# attinier85-motherboard-smd-mk-2_2.net
KiCad netlist of a schematic drawn in EAGLE
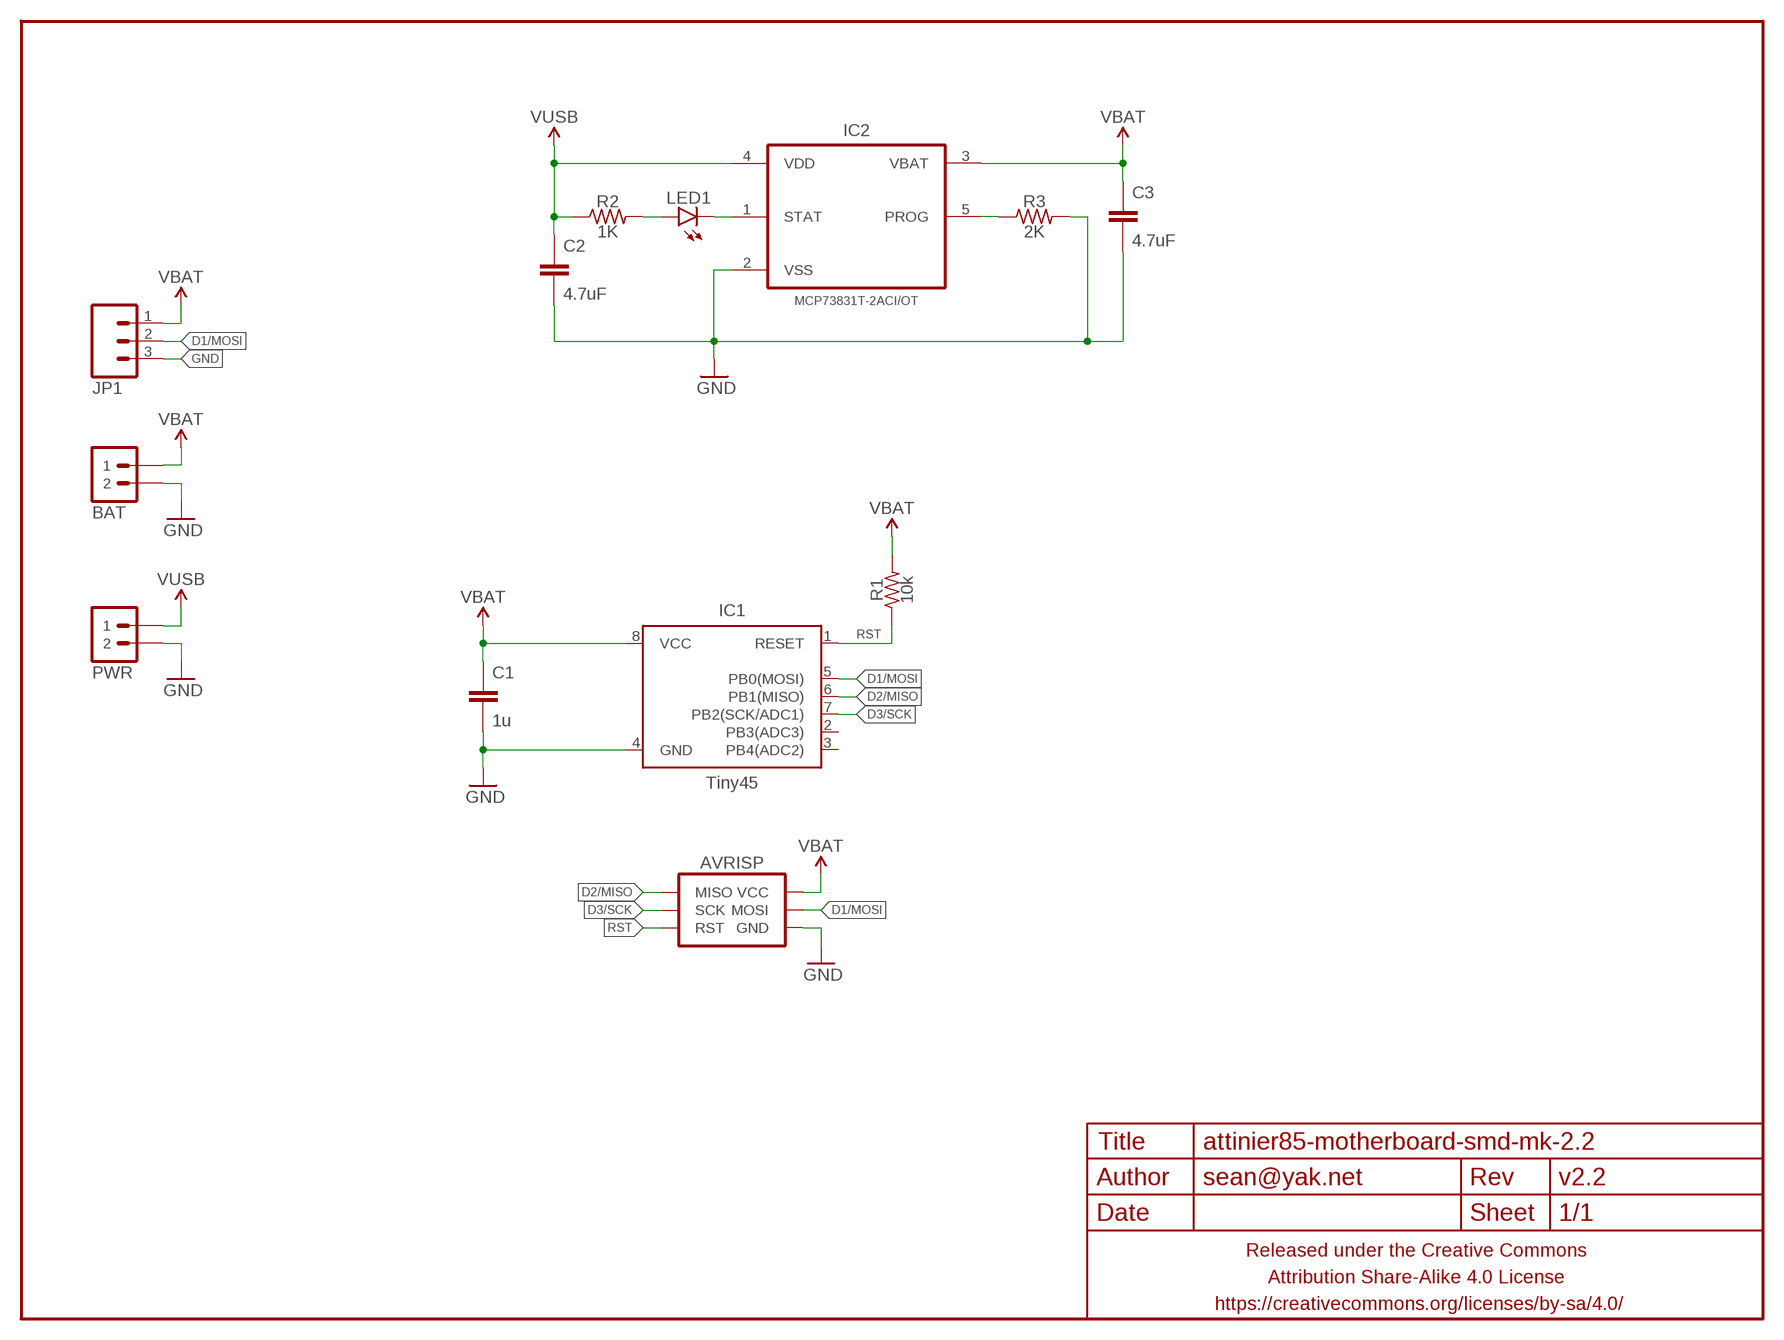
[diagram p0: schematic, sheet 1]

(export (version "E")
  (design (tool "Eeschema 10.0.6"))
  (components
    (comp (ref "AVRISP")
      (value "AVR_SPI_PRG_6SMD_TEST_POINTS")
      (footprint "eagle-import:2X3_SMD_TEST_POINTS")
      (libsource (lib "eagle-import") (part "AVR_SPI_PRG_6SMD_TEST_POINTS"))
    )
    (comp (ref "BAT")
      (value "M02PTH-CENTERED")
      (footprint "eagle-import:1X02-CENTER")
      (libsource (lib "eagle-import") (part "M02PTH-CENTERED"))
    )
    (comp (ref "C1")
      (value "1u")
      (footprint "eagle-import:C0603-TIGHTER")
      (libsource (lib "eagle-import") (part "CAPACITOR-CERAMICC0603-TIGHTER"))
    )
    (comp (ref "C2")
      (value "4.7uF")
      (footprint "eagle-import:C0603-TIGHTER")
      (libsource (lib "eagle-import") (part "CAPACITOR-CERAMICC0603-TIGHTER"))
    )
    (comp (ref "C3")
      (value "4.7uF")
      (footprint "eagle-import:C0603-TIGHTER")
      (libsource (lib "eagle-import") (part "CAPACITOR-CERAMICC0603-TIGHTER"))
    )
    (comp (ref "FRAME1")
      (value "FRAME-LETTERNO_PACKAGE")
      (footprint "eagle-import:DUMMY")
      (fields (field (name "DESIGNER") "sean@yak.net") (field (name "VERSION") "v2.2"))
      (libsource (lib "eagle-import") (part "FRAME-LETTERNO_PACKAGE"))
    )
    (comp (ref "IC1")
      (value "Tiny45")
      (footprint "eagle-import:SO08")
      (libsource (lib "eagle-import") (part "ATTINY45TINY25-20-SOICN"))
    )
    (comp (ref "IC2")
      (value "MCP73831T-2ACI/OT")
      (footprint "eagle-import:SOT95P280X145-5N")
      (libsource (lib "eagle-import") (part "MCP73831T-2ACI/OT"))
    )
    (comp (ref "JP1")
      (value "M03PTH-CENTERED")
      (footprint "eagle-import:1X03-CENTERED")
      (libsource (lib "eagle-import") (part "M03PTH-CENTERED"))
    )
    (comp (ref "LED1")
      (value "LED0603-TIGHT")
      (footprint "eagle-import:LED-0603-TIGHT")
      (libsource (lib "eagle-import") (part "LED0603-TIGHT"))
    )
    (comp (ref "PWR")
      (value "M02PTH-CENTERED")
      (footprint "eagle-import:1X02-CENTER")
      (libsource (lib "eagle-import") (part "M02PTH-CENTERED"))
    )
    (comp (ref "R1")
      (value "10k")
      (footprint "eagle-import:R0603-TIGHTER")
      (libsource (lib "eagle-import") (part "RESISTORR0603-TIGHTER"))
    )
    (comp (ref "R2")
      (value "1K")
      (footprint "eagle-import:R0603-TIGHTER")
      (libsource (lib "eagle-import") (part "RESISTORR0603-TIGHTER"))
    )
    (comp (ref "R3")
      (value "2K")
      (footprint "eagle-import:R0603-TIGHTER")
      (libsource (lib "eagle-import") (part "RESISTORR0603-TIGHTER"))
    )
  )
  (nets
    (net (code "1") (name "D1{slash}MOSI") (class "Default")
      (node (ref "AVRISP") (pin "4") (pinfunction "MOSI_4") (pintype "passive"))
      (node (ref "IC1") (pin "5") (pinfunction "PB0(MOSI)_5") (pintype "bidirectional"))
      (node (ref "JP1") (pin "2") (pinfunction "2_2") (pintype "passive"))
    )
    (net (code "2") (name "D2{slash}MISO") (class "Default")
      (node (ref "AVRISP") (pin "1") (pinfunction "MISO_1") (pintype "passive"))
      (node (ref "IC1") (pin "6") (pinfunction "PB1(MISO)_6") (pintype "bidirectional"))
    )
    (net (code "3") (name "D3{slash}SCK") (class "Default")
      (node (ref "AVRISP") (pin "3") (pinfunction "SCK_3") (pintype "passive"))
      (node (ref "IC1") (pin "7") (pinfunction "PB2(SCK/ADC1)_7") (pintype "bidirectional"))
    )
    (net (code "4") (name "GND") (class "Default")
      (node (ref "AVRISP") (pin "6") (pinfunction "GND_6") (pintype "passive"))
      (node (ref "BAT") (pin "2") (pinfunction "2_2") (pintype "passive"))
      (node (ref "C1") (pin "2") (pinfunction "2_2") (pintype "passive"))
      (node (ref "C2") (pin "2") (pinfunction "2_2") (pintype "passive"))
      (node (ref "C3") (pin "2") (pinfunction "2_2") (pintype "passive"))
      (node (ref "IC1") (pin "4") (pinfunction "GND_4") (pintype "bidirectional"))
      (node (ref "IC2") (pin "2") (pinfunction "VSS_2") (pintype "power_in"))
      (node (ref "JP1") (pin "3") (pinfunction "3_3") (pintype "passive"))
      (node (ref "PWR") (pin "2") (pinfunction "2_2") (pintype "passive"))
      (node (ref "R3") (pin "2") (pinfunction "2_2") (pintype "passive"))
    )
    (net (code "5") (name "Net-(IC2-PROG)") (class "Default")
      (node (ref "IC2") (pin "5") (pinfunction "PROG_5") (pintype "input"))
      (node (ref "R3") (pin "1") (pinfunction "1_1") (pintype "passive"))
    )
    (net (code "6") (name "Net-(IC2-STAT)") (class "Default")
      (node (ref "IC2") (pin "1") (pinfunction "STAT_1") (pintype "output"))
      (node (ref "LED1") (pin "C") (pinfunction "C_C") (pintype "passive"))
    )
    (net (code "7") (name "Net-(LED1-PadA)") (class "Default")
      (node (ref "LED1") (pin "A") (pinfunction "A_A") (pintype "passive"))
      (node (ref "R2") (pin "2") (pinfunction "2_2") (pintype "passive"))
    )
    (net (code "8") (name "RST") (class "Default")
      (node (ref "AVRISP") (pin "5") (pinfunction "RST_5") (pintype "passive"))
      (node (ref "IC1") (pin "1") (pinfunction "RESET_1") (pintype "bidirectional"))
      (node (ref "R1") (pin "1") (pinfunction "1_1") (pintype "passive"))
    )
    (net (code "9") (name "VBAT") (class "Default")
      (node (ref "AVRISP") (pin "2") (pinfunction "VCC_2") (pintype "passive"))
      (node (ref "BAT") (pin "1") (pinfunction "1_1") (pintype "passive"))
      (node (ref "C1") (pin "1") (pinfunction "1_1") (pintype "passive"))
      (node (ref "C3") (pin "1") (pinfunction "1_1") (pintype "passive"))
      (node (ref "IC1") (pin "8") (pinfunction "VCC_8") (pintype "bidirectional"))
      (node (ref "IC2") (pin "3") (pinfunction "VBAT_3") (pintype "output"))
      (node (ref "JP1") (pin "1") (pinfunction "1_1") (pintype "passive"))
      (node (ref "R1") (pin "2") (pinfunction "2_2") (pintype "passive"))
    )
    (net (code "10") (name "VUSB") (class "Default")
      (node (ref "C2") (pin "1") (pinfunction "1_1") (pintype "passive"))
      (node (ref "IC2") (pin "4") (pinfunction "VDD_4") (pintype "power_in"))
      (node (ref "PWR") (pin "1") (pinfunction "1_1") (pintype "passive"))
      (node (ref "R2") (pin "1") (pinfunction "1_1") (pintype "passive"))
    )
    (net (code "11") (name "unconnected-(IC1-PB3(ADC3)-Pad2)") (class "Default")
      (node (ref "IC1") (pin "2") (pinfunction "PB3(ADC3)_2") (pintype "bidirectional"))
    )
    (net (code "12") (name "unconnected-(IC1-PB4(ADC2)-Pad3)") (class "Default")
      (node (ref "IC1") (pin "3") (pinfunction "PB4(ADC2)_3") (pintype "bidirectional"))
    )
  )
)
